# Supply_0_V1_01.net
KiCad netlist of a schematic drawn in Altium Designer
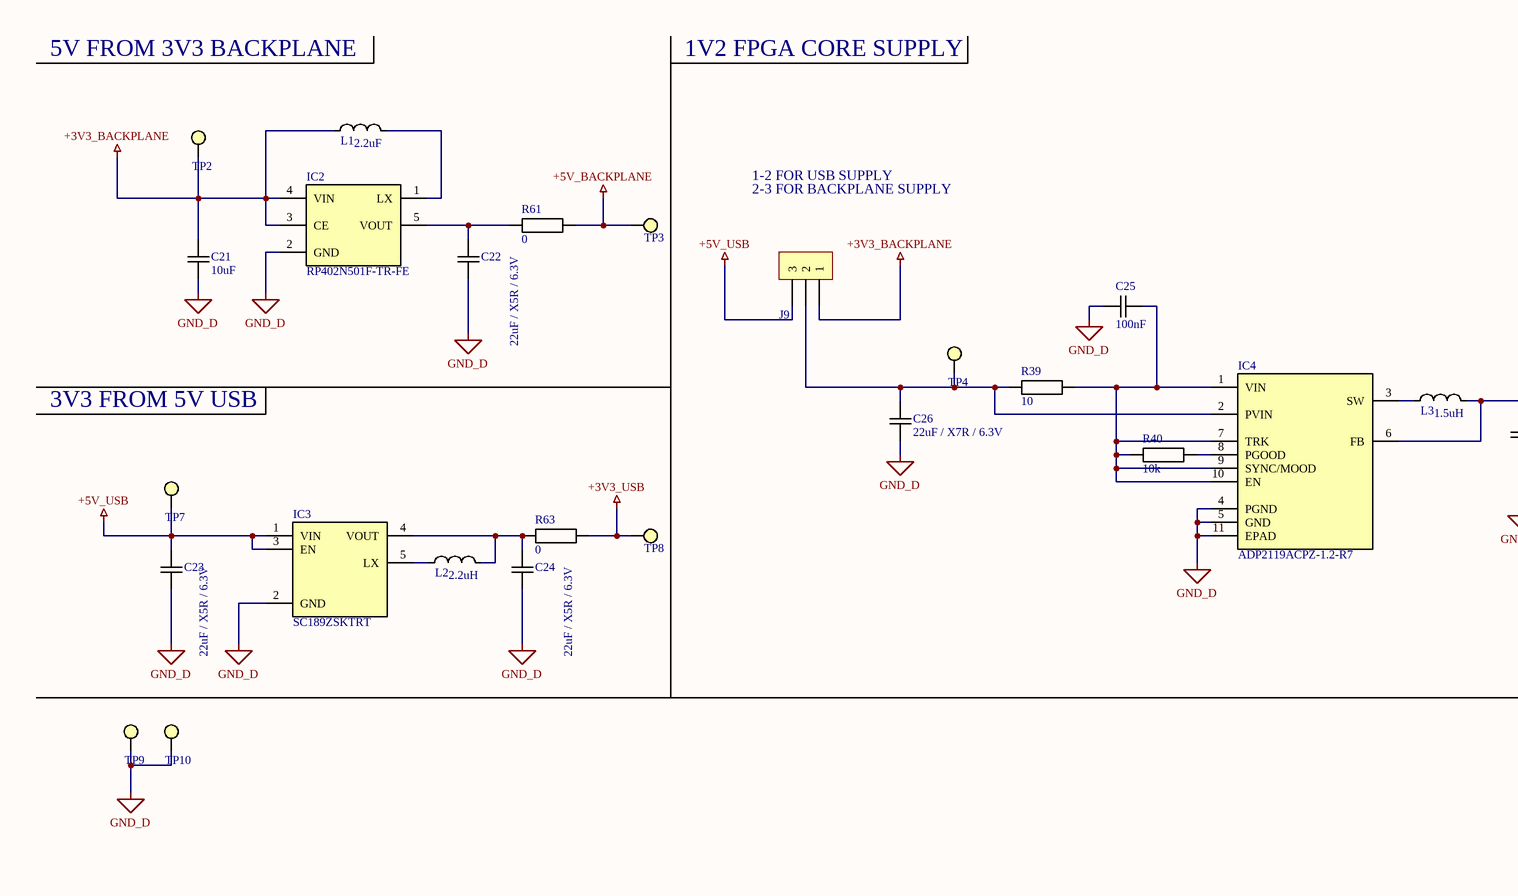
[diagram p0: Supply_0_V1_01.SchDoc, left]
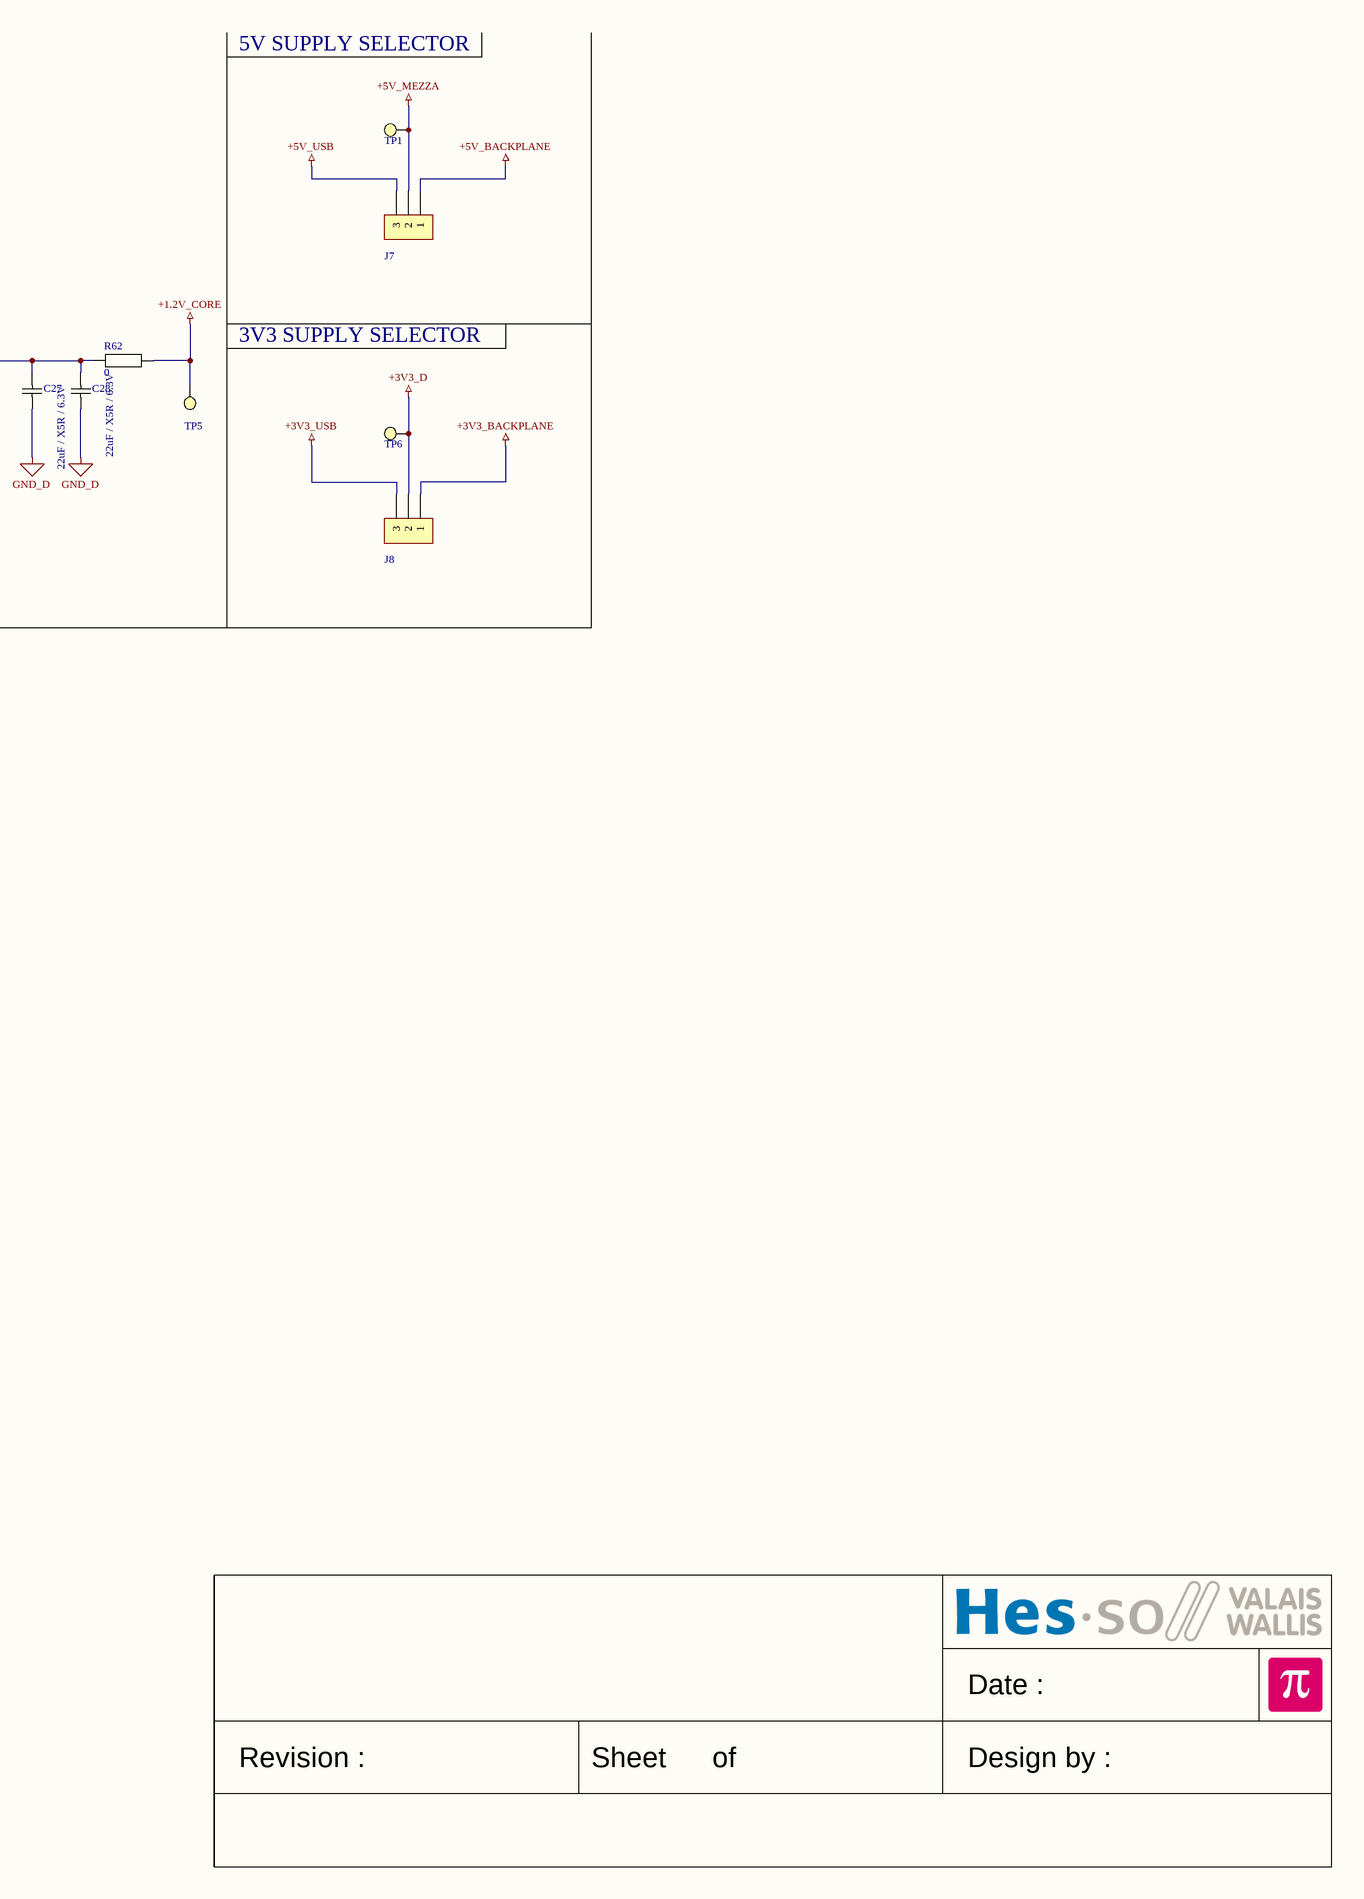
[diagram p1: Supply_0_V1_01.SchDoc, right]

(export (version "E")
  (design (tool "Eeschema 10.0.6"))
  (components
    (comp (ref "C21")
      (value "10uF")
      (footprint "CAPACITOR 2012 REFLOW")
      (description "Capacitor")
      (libsource (lib "Capacitor") (part "Capacitor"))
    )
    (comp (ref "C22")
      (value "22uF / X5R / 6.3V")
      (footprint "CAPACITOR 2012 REFLOW")
      (description "Capacitor")
      (libsource (lib "Capacitor") (part "Capacitor"))
    )
    (comp (ref "C23")
      (value "22uF / X5R / 6.3V")
      (footprint "CAPACITOR 2012 REFLOW")
      (description "Capacitor")
      (libsource (lib "Capacitor") (part "Capacitor"))
    )
    (comp (ref "C24")
      (value "22uF / X5R / 6.3V")
      (footprint "CAPACITOR 2012 REFLOW")
      (description "Capacitor")
      (libsource (lib "Capacitor") (part "Capacitor"))
    )
    (comp (ref "C25")
      (value "100nF")
      (footprint "CAPACITOR 1608 REFLOW")
      (description "Capacitor")
      (libsource (lib "Capacitor") (part "Capacitor"))
    )
    (comp (ref "C26")
      (value "22uF / X7R / 6.3V")
      (footprint "CAPACITOR 2012 REFLOW")
      (description "Capacitor")
      (libsource (lib "Capacitor") (part "Capacitor"))
    )
    (comp (ref "C27")
      (value "22uF / X5R / 6.3V")
      (footprint "CAPACITOR 2012 REFLOW")
      (description "Capacitor")
      (libsource (lib "Capacitor") (part "Capacitor"))
    )
    (comp (ref "C28")
      (value "22uF / X5R / 6.3V")
      (footprint "CAPACITOR 2012 REFLOW")
      (description "Capacitor")
      (libsource (lib "Capacitor") (part "Capacitor"))
    )
    (comp (ref "IC2")
      (value "RP402N501F-TR-FE")
      (footprint "SamacSys:SOT95P280X130-5N")
      (description "Integrated Circuit")
      (fields (field (name "MOUSER PART NUMBER") "848-RP402N501F-TR-FE"))
      (libsource (lib "SamacSys") (part "RP402N501F-TR-FE"))
    )
    (comp (ref "IC3")
      (value "SC189ZSKTRT")
      (footprint "SamacSys:SOT95P280X145-5N")
      (description "Integrated Circuit")
      (fields (field (name "MOUSER PART NUMBER") "947-SC189ZSKTRT"))
      (libsource (lib "SamacSys") (part "SC189ZSKTRT"))
    )
    (comp (ref "IC4")
      (value "ADP2119ACPZ-1.2-R7")
      (footprint "SamacSys:SON50P300X300X85-11N")
      (description "Integrated Circuit")
      (fields (field (name "MOUSER PART NUMBER") "584-ADP2119ACPZ1.2R7"))
      (libsource (lib "SamacSys") (part "ADP2119ACPZ-1.2-R7"))
    )
    (comp (ref "J7")
      (value "*")
      (footprint "PinHeader1x3 P2.54")
      (description "Plug connector")
      (libsource (lib "PinHeader") (part "PinHeader1x3"))
    )
    (comp (ref "J8")
      (value "*")
      (footprint "PinHeader1x3 P2.54")
      (description "Plug connector")
      (libsource (lib "PinHeader") (part "PinHeader1x3"))
    )
    (comp (ref "J9")
      (value "*")
      (footprint "PinHeader1x3 P2.54")
      (description "Plug connector")
      (libsource (lib "") (part "PinHeader1x3_1"))
    )
    (comp (ref "L1")
      (value "2.2uF")
      (footprint "TDK VLCF5020-1")
      (description "Inductor")
      (libsource (lib "Inductor") (part "Inductor"))
    )
    (comp (ref "L2")
      (value "2.2uH")
      (footprint "TDK VLCF5020-1")
      (description "Inductor")
      (libsource (lib "Inductor") (part "Inductor"))
    )
    (comp (ref "L3")
      (value "1.5uH")
      (footprint "TDK VLCF5020-1")
      (description "Inductor")
      (libsource (lib "Inductor") (part "Inductor"))
    )
    (comp (ref "R39")
      (value "10")
      (footprint "RESISTOR 2012 REFLOW")
      (description "Resistor 1% 50V 125mW 2012(0805)")
      (libsource (lib "Resistor") (part "Resistor"))
    )
    (comp (ref "R40")
      (value "10k")
      (footprint "RESISTOR 1608 REFLOW")
      (description "Resistor 1% 50V 125mW 2012(0805)")
      (libsource (lib "Resistor") (part "Resistor"))
    )
    (comp (ref "R61")
      (value "0")
      (footprint "RESISTOR 1608 REFLOW")
      (description "Resistor 1% 50V 100mW 1608(0603)")
      (libsource (lib "Resistor") (part "Resistor"))
    )
    (comp (ref "R62")
      (value "0")
      (footprint "RESISTOR 1608 REFLOW")
      (description "Resistor 1% 50V 100mW 1608(0603)")
      (libsource (lib "Resistor") (part "Resistor"))
    )
    (comp (ref "R63")
      (value "0")
      (footprint "RESISTOR 1608 REFLOW")
      (description "Resistor 1% 50V 100mW 1608(0603)")
      (libsource (lib "Resistor") (part "Resistor"))
    )
    (comp (ref "TP1")
      (value "*")
      (footprint "Test Point Keystone Miniature RED")
      (description "Test Point")
      (libsource (lib "Testpoint") (part "Test Point"))
    )
    (comp (ref "TP2")
      (value "*")
      (footprint "Test Point Keystone Miniature RED")
      (description "Test Point")
      (libsource (lib "Testpoint") (part "Test Point"))
    )
    (comp (ref "TP3")
      (value "*")
      (footprint "Test Point Keystone Miniature RED")
      (description "Test Point")
      (libsource (lib "Testpoint") (part "Test Point"))
    )
    (comp (ref "TP4")
      (value "*")
      (footprint "Test Point Keystone Miniature RED")
      (description "Test Point")
      (libsource (lib "Testpoint") (part "Test Point"))
    )
    (comp (ref "TP5")
      (value "*")
      (footprint "Test Point Keystone Miniature RED")
      (description "Test Point")
      (libsource (lib "Testpoint") (part "Test Point"))
    )
    (comp (ref "TP6")
      (value "*")
      (footprint "Test Point Keystone Miniature RED")
      (description "Test Point")
      (libsource (lib "Testpoint") (part "Test Point"))
    )
    (comp (ref "TP7")
      (value "*")
      (footprint "Test Point Keystone Miniature RED")
      (description "Test Point")
      (libsource (lib "Testpoint") (part "Test Point"))
    )
    (comp (ref "TP8")
      (value "*")
      (footprint "Test Point Keystone Miniature RED")
      (description "Test Point")
      (libsource (lib "Testpoint") (part "Test Point"))
    )
    (comp (ref "TP9")
      (value "*")
      (footprint "Test Point Keystone Miniature BLACK")
      (description "Test Point")
      (libsource (lib "Testpoint") (part "Test Point"))
    )
    (comp (ref "TP10")
      (value "*")
      (footprint "Test Point Keystone Miniature BLACK")
      (description "Test Point")
      (libsource (lib "Testpoint") (part "Test Point"))
    )
  )
  (nets
    (net (code "1") (name "+1.2V_CORE") (class "Default")
      (node (ref "R62") (pin "2") (pinfunction "2_2") (pintype "passive"))
      (node (ref "TP5") (pin "1") (pinfunction "1_1") (pintype "passive"))
    )
    (net (code "2") (name "+3V3_BACKPLANE") (class "Default")
      (node (ref "C21") (pin "2") (pinfunction "2_2") (pintype "passive"))
      (node (ref "IC2") (pin "3") (pinfunction "CE_3") (pintype "passive"))
      (node (ref "IC2") (pin "4") (pinfunction "VIN_4") (pintype "passive"))
      (node (ref "J8") (pin "1") (pinfunction "1_1") (pintype "passive"))
      (node (ref "J9") (pin "1") (pinfunction "1_1") (pintype "passive"))
      (node (ref "L1") (pin "1") (pinfunction "1_1") (pintype "passive"))
      (node (ref "TP2") (pin "1") (pinfunction "1_1") (pintype "passive"))
    )
    (net (code "3") (name "+3V3_D") (class "Default")
      (node (ref "J8") (pin "2") (pinfunction "2_2") (pintype "passive"))
      (node (ref "TP6") (pin "1") (pinfunction "1_1") (pintype "passive"))
    )
    (net (code "4") (name "+3V3_USB") (class "Default")
      (node (ref "J8") (pin "3") (pinfunction "3_3") (pintype "passive"))
      (node (ref "R63") (pin "2") (pinfunction "2_2") (pintype "passive"))
      (node (ref "TP8") (pin "1") (pinfunction "1_1") (pintype "passive"))
    )
    (net (code "5") (name "+5V_BACKPLANE") (class "Default")
      (node (ref "J7") (pin "1") (pinfunction "1_1") (pintype "passive"))
      (node (ref "R61") (pin "2") (pinfunction "2_2") (pintype "passive"))
      (node (ref "TP3") (pin "1") (pinfunction "1_1") (pintype "passive"))
    )
    (net (code "6") (name "+5V_MEZZA") (class "Default")
      (node (ref "J7") (pin "2") (pinfunction "2_2") (pintype "passive"))
      (node (ref "TP1") (pin "1") (pinfunction "1_1") (pintype "passive"))
    )
    (net (code "7") (name "+5V_USB") (class "Default")
      (node (ref "C23") (pin "2") (pinfunction "2_2") (pintype "passive"))
      (node (ref "IC3") (pin "1") (pinfunction "VIN_1") (pintype "passive"))
      (node (ref "IC3") (pin "3") (pinfunction "EN_3") (pintype "passive"))
      (node (ref "J7") (pin "3") (pinfunction "3_3") (pintype "passive"))
      (node (ref "J9") (pin "3") (pinfunction "3_3") (pintype "passive"))
      (node (ref "TP7") (pin "1") (pinfunction "1_1") (pintype "passive"))
    )
    (net (code "8") (name "GND_D") (class "Default")
      (node (ref "C21") (pin "1") (pinfunction "1_1") (pintype "passive"))
      (node (ref "C22") (pin "1") (pinfunction "1_1") (pintype "passive"))
      (node (ref "C23") (pin "1") (pinfunction "1_1") (pintype "passive"))
      (node (ref "C24") (pin "1") (pinfunction "1_1") (pintype "passive"))
      (node (ref "C25") (pin "2") (pinfunction "2_2") (pintype "passive"))
      (node (ref "C26") (pin "1") (pinfunction "1_1") (pintype "passive"))
      (node (ref "C27") (pin "1") (pinfunction "1_1") (pintype "passive"))
      (node (ref "C28") (pin "1") (pinfunction "1_1") (pintype "passive"))
      (node (ref "IC2") (pin "2") (pinfunction "GND_2") (pintype "passive"))
      (node (ref "IC3") (pin "2") (pinfunction "GND_2") (pintype "passive"))
      (node (ref "IC4") (pin "11") (pinfunction "EPAD_11") (pintype "passive"))
      (node (ref "IC4") (pin "4") (pinfunction "PGND_4") (pintype "passive"))
      (node (ref "IC4") (pin "5") (pinfunction "GND_5") (pintype "passive"))
      (node (ref "TP10") (pin "1") (pinfunction "1_1") (pintype "passive"))
      (node (ref "TP9") (pin "1") (pinfunction "1_1") (pintype "passive"))
    )
    (net (code "9") (name "Net-(IC2-LX)") (class "Default")
      (node (ref "IC2") (pin "1") (pinfunction "LX_1") (pintype "passive"))
      (node (ref "L1") (pin "2") (pinfunction "2_2") (pintype "passive"))
    )
    (net (code "10") (name "Net-(IC2-VOUT)") (class "Default")
      (node (ref "C22") (pin "2") (pinfunction "2_2") (pintype "passive"))
      (node (ref "IC2") (pin "5") (pinfunction "VOUT_5") (pintype "passive"))
      (node (ref "R61") (pin "1") (pinfunction "1_1") (pintype "passive"))
    )
    (net (code "11") (name "Net-(IC3-LX)") (class "Default")
      (node (ref "IC3") (pin "5") (pinfunction "LX_5") (pintype "passive"))
      (node (ref "L2") (pin "1") (pinfunction "1_1") (pintype "passive"))
    )
    (net (code "12") (name "Net-(IC3-VOUT)") (class "Default")
      (node (ref "C24") (pin "2") (pinfunction "2_2") (pintype "passive"))
      (node (ref "IC3") (pin "4") (pinfunction "VOUT_4") (pintype "passive"))
      (node (ref "L2") (pin "2") (pinfunction "2_2") (pintype "passive"))
      (node (ref "R63") (pin "1") (pinfunction "1_1") (pintype "passive"))
    )
    (net (code "13") (name "Net-(IC4-EN)") (class "Default")
      (node (ref "C25") (pin "1") (pinfunction "1_1") (pintype "passive"))
      (node (ref "IC4") (pin "1") (pinfunction "VIN_1") (pintype "passive"))
      (node (ref "IC4") (pin "10") (pinfunction "EN_10") (pintype "passive"))
      (node (ref "IC4") (pin "7") (pinfunction "TRK_7") (pintype "passive"))
      (node (ref "IC4") (pin "9") (pinfunction "SYNC/MOOD_9") (pintype "passive"))
      (node (ref "R39") (pin "1") (pinfunction "1_1") (pintype "passive"))
      (node (ref "R40") (pin "2") (pinfunction "2_2") (pintype "passive"))
    )
    (net (code "14") (name "Net-(IC4-FB)") (class "Default")
      (node (ref "C27") (pin "2") (pinfunction "2_2") (pintype "passive"))
      (node (ref "C28") (pin "2") (pinfunction "2_2") (pintype "passive"))
      (node (ref "IC4") (pin "6") (pinfunction "FB_6") (pintype "passive"))
      (node (ref "L3") (pin "2") (pinfunction "2_2") (pintype "passive"))
      (node (ref "R62") (pin "1") (pinfunction "1_1") (pintype "passive"))
    )
    (net (code "15") (name "Net-(IC4-PGOOD)") (class "Default")
      (node (ref "IC4") (pin "8") (pinfunction "PGOOD_8") (pintype "passive"))
      (node (ref "R40") (pin "1") (pinfunction "1_1") (pintype "passive"))
    )
    (net (code "16") (name "Net-(IC4-PVIN)") (class "Default")
      (node (ref "C26") (pin "2") (pinfunction "2_2") (pintype "passive"))
      (node (ref "IC4") (pin "2") (pinfunction "PVIN_2") (pintype "passive"))
      (node (ref "J9") (pin "2") (pinfunction "2_2") (pintype "passive"))
      (node (ref "R39") (pin "2") (pinfunction "2_2") (pintype "passive"))
      (node (ref "TP4") (pin "1") (pinfunction "1_1") (pintype "passive"))
    )
    (net (code "17") (name "Net-(IC4-SW)") (class "Default")
      (node (ref "IC4") (pin "3") (pinfunction "SW_3") (pintype "passive"))
      (node (ref "L3") (pin "1") (pinfunction "1_1") (pintype "passive"))
    )
  )
)
